# Analogs.net
KiCad netlist of a schematic drawn in Altium Designer
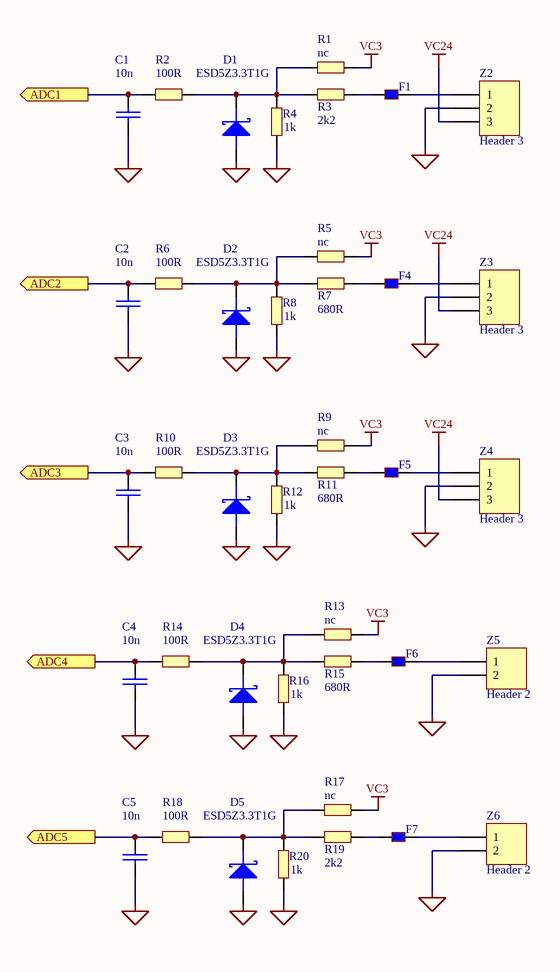
[diagram p0: Analogs.SchDoc]

(export (version "E")
  (design (tool "Eeschema 10.0.6"))
  (components
    (comp (ref "C1")
      (value "10n")
      (footprint "0805C")
      (description "Capacitor")
      (libsource (lib "*") (part "CAP"))
    )
    (comp (ref "C2")
      (value "10n")
      (footprint "0805C")
      (description "Capacitor")
      (libsource (lib "*") (part "CAP"))
    )
    (comp (ref "C3")
      (value "10n")
      (footprint "0805C")
      (description "Capacitor")
      (libsource (lib "*") (part "CAP"))
    )
    (comp (ref "C4")
      (value "10n")
      (footprint "0805C")
      (description "Capacitor")
      (libsource (lib "*") (part "CAP"))
    )
    (comp (ref "C5")
      (value "10n")
      (footprint "0805C")
      (description "Capacitor")
      (libsource (lib "*") (part "CAP"))
    )
    (comp (ref "D1")
      (value "ESD5Z3.3T1G")
      (footprint "SOD_523")
      (libsource (lib "*") (part "DIODE SCHOTTKY"))
    )
    (comp (ref "D2")
      (value "ESD5Z3.3T1G")
      (footprint "SOD_523")
      (libsource (lib "*") (part "DIODE SCHOTTKY"))
    )
    (comp (ref "D3")
      (value "ESD5Z3.3T1G")
      (footprint "SOD_523")
      (libsource (lib "*") (part "DIODE SCHOTTKY"))
    )
    (comp (ref "D4")
      (value "ESD5Z3.3T1G")
      (footprint "SOD_523")
      (libsource (lib "*") (part "DIODE SCHOTTKY"))
    )
    (comp (ref "D5")
      (value "ESD5Z3.3T1G")
      (footprint "SOD_523")
      (libsource (lib "*") (part "DIODE SCHOTTKY"))
    )
    (comp (ref "F1")
      (value "BLM18BB141SN1D")
      (footprint "0805L")
      (description "Koralik ferrytowy")
      (libsource (lib "*") (part "1812"))
    )
    (comp (ref "F4")
      (value "BLM18BB141SN1D")
      (footprint "0805L")
      (description "Koralik ferrytowy")
      (libsource (lib "*") (part "1812"))
    )
    (comp (ref "F5")
      (value "BLM18BB141SN1D")
      (footprint "0805L")
      (description "Koralik ferrytowy")
      (libsource (lib "*") (part "1812"))
    )
    (comp (ref "F6")
      (value "BLM18BB141SN1D")
      (footprint "0805L")
      (description "Koralik ferrytowy")
      (libsource (lib "*") (part "1812"))
    )
    (comp (ref "F7")
      (value "BLM18BB141SN1D")
      (footprint "0805L")
      (description "Koralik ferrytowy")
      (libsource (lib "*") (part "1812"))
    )
    (comp (ref "R1") (value "nc") (footprint "0805R") (libsource (lib "*") (part "RES3")))
    (comp (ref "R2") (value "100R") (footprint "0805R") (libsource (lib "") (part "RES3_2")))
    (comp (ref "R3") (value "2k2") (footprint "0805R") (libsource (lib "*") (part "RES3")))
    (comp (ref "R4") (value "1k") (footprint "0805R") (libsource (lib "") (part "RES3_1")))
    (comp (ref "R5") (value "nc") (footprint "0805R") (libsource (lib "*") (part "RES3")))
    (comp (ref "R6") (value "100R") (footprint "0805R") (libsource (lib "") (part "RES3_2")))
    (comp (ref "R7") (value "680R") (footprint "0805R") (libsource (lib "*") (part "RES3")))
    (comp (ref "R8") (value "1k") (footprint "0805R") (libsource (lib "") (part "RES3_1")))
    (comp (ref "R9") (value "nc") (footprint "0805R") (libsource (lib "*") (part "RES3")))
    (comp (ref "R10") (value "100R") (footprint "0805R") (libsource (lib "") (part "RES3_2")))
    (comp (ref "R11") (value "680R") (footprint "0805R") (libsource (lib "*") (part "RES3")))
    (comp (ref "R12") (value "1k") (footprint "0805R") (libsource (lib "") (part "RES3_1")))
    (comp (ref "R13") (value "nc") (footprint "0805R") (libsource (lib "*") (part "RES3")))
    (comp (ref "R14") (value "100R") (footprint "0805R") (libsource (lib "") (part "RES3_2")))
    (comp (ref "R15") (value "680R") (footprint "0805R") (libsource (lib "*") (part "RES3")))
    (comp (ref "R16") (value "1k") (footprint "0805R") (libsource (lib "") (part "RES3_1")))
    (comp (ref "R17") (value "nc") (footprint "0805R") (libsource (lib "*") (part "RES3")))
    (comp (ref "R18") (value "100R") (footprint "0805R") (libsource (lib "") (part "RES3_2")))
    (comp (ref "R19") (value "2k2") (footprint "0805R") (libsource (lib "*") (part "RES3")))
    (comp (ref "R20") (value "1k") (footprint "0805R") (libsource (lib "") (part "RES3_1")))
    (comp (ref "Z2")
      (value "Header 3")
      (footprint "ARC-L-3-3.5")
      (description "Header, 3-Pin")
      (fields (field (name "PUBLISHER") "Altium Limited"))
      (libsource (lib "Miscellaneous Connectors") (part "Header 3"))
    )
    (comp (ref "Z3")
      (value "Header 3")
      (footprint "ARC-L-3-3.5")
      (description "Header, 3-Pin")
      (fields (field (name "PUBLISHER") "Altium Limited"))
      (libsource (lib "Miscellaneous Connectors") (part "Header 3"))
    )
    (comp (ref "Z4")
      (value "Header 3")
      (footprint "ARC-L-3-3.5")
      (description "Header, 3-Pin")
      (fields (field (name "PUBLISHER") "Altium Limited"))
      (libsource (lib "Miscellaneous Connectors") (part "Header 3"))
    )
    (comp (ref "Z5")
      (value "Header 2")
      (footprint "ARC-L-2-3.5")
      (description "Header, 2-Pin")
      (fields (field (name "PUBLISHER") "Altium Limited"))
      (libsource (lib "Miscellaneous Connectors") (part "Header 2"))
    )
    (comp (ref "Z6")
      (value "Header 2")
      (footprint "ARC-L-2-3.5")
      (description "Header, 2-Pin")
      (fields (field (name "PUBLISHER") "Altium Limited"))
      (libsource (lib "Miscellaneous Connectors") (part "Header 2"))
    )
  )
  (nets
    (net (code "1") (name "/ADC1") (class "Default")
      (node (ref "C1") (pin "1") (pinfunction "1_1") (pintype "passive"))
      (node (ref "R2") (pin "1") (pintype "passive"))
    )
    (net (code "2") (name "/ADC2") (class "Default")
      (node (ref "C2") (pin "1") (pinfunction "1_1") (pintype "passive"))
      (node (ref "R6") (pin "1") (pintype "passive"))
    )
    (net (code "3") (name "/ADC3") (class "Default")
      (node (ref "C3") (pin "1") (pinfunction "1_1") (pintype "passive"))
      (node (ref "R10") (pin "1") (pintype "passive"))
    )
    (net (code "4") (name "/ADC4") (class "Default")
      (node (ref "C4") (pin "1") (pinfunction "1_1") (pintype "passive"))
      (node (ref "R14") (pin "1") (pintype "passive"))
    )
    (net (code "5") (name "/ADC5") (class "Default")
      (node (ref "C5") (pin "1") (pinfunction "1_1") (pintype "passive"))
      (node (ref "R18") (pin "1") (pintype "passive"))
    )
    (net (code "6") (name "AGND") (class "Default")
      (node (ref "C1") (pin "2") (pinfunction "2_2") (pintype "passive"))
      (node (ref "C2") (pin "2") (pinfunction "2_2") (pintype "passive"))
      (node (ref "C3") (pin "2") (pinfunction "2_2") (pintype "passive"))
      (node (ref "C4") (pin "2") (pinfunction "2_2") (pintype "passive"))
      (node (ref "C5") (pin "2") (pinfunction "2_2") (pintype "passive"))
      (node (ref "D1") (pin "A") (pinfunction "A_A") (pintype "passive"))
      (node (ref "D2") (pin "A") (pinfunction "A_A") (pintype "passive"))
      (node (ref "D3") (pin "A") (pinfunction "A_A") (pintype "passive"))
      (node (ref "D4") (pin "A") (pinfunction "A_A") (pintype "passive"))
      (node (ref "D5") (pin "A") (pinfunction "A_A") (pintype "passive"))
      (node (ref "R12") (pin "1") (pintype "passive"))
      (node (ref "R16") (pin "1") (pintype "passive"))
      (node (ref "R20") (pin "1") (pintype "passive"))
      (node (ref "R4") (pin "1") (pintype "passive"))
      (node (ref "R8") (pin "1") (pintype "passive"))
      (node (ref "Z2") (pin "2") (pinfunction "2_2") (pintype "passive"))
      (node (ref "Z3") (pin "2") (pinfunction "2_2") (pintype "passive"))
      (node (ref "Z4") (pin "2") (pinfunction "2_2") (pintype "passive"))
      (node (ref "Z5") (pin "2") (pinfunction "2_2") (pintype "passive"))
      (node (ref "Z6") (pin "2") (pinfunction "2_2") (pintype "passive"))
    )
    (net (code "7") (name "Net-(D1-PadK)") (class "Default")
      (node (ref "D1") (pin "K") (pinfunction "K_K") (pintype "passive"))
      (node (ref "R1") (pin "2") (pintype "passive"))
      (node (ref "R2") (pin "2") (pintype "passive"))
      (node (ref "R3") (pin "2") (pintype "passive"))
      (node (ref "R4") (pin "2") (pintype "passive"))
    )
    (net (code "8") (name "Net-(D2-PadK)") (class "Default")
      (node (ref "D2") (pin "K") (pinfunction "K_K") (pintype "passive"))
      (node (ref "R5") (pin "2") (pintype "passive"))
      (node (ref "R6") (pin "2") (pintype "passive"))
      (node (ref "R7") (pin "2") (pintype "passive"))
      (node (ref "R8") (pin "2") (pintype "passive"))
    )
    (net (code "9") (name "Net-(D3-PadK)") (class "Default")
      (node (ref "D3") (pin "K") (pinfunction "K_K") (pintype "passive"))
      (node (ref "R10") (pin "2") (pintype "passive"))
      (node (ref "R11") (pin "2") (pintype "passive"))
      (node (ref "R12") (pin "2") (pintype "passive"))
      (node (ref "R9") (pin "2") (pintype "passive"))
    )
    (net (code "10") (name "Net-(D4-PadK)") (class "Default")
      (node (ref "D4") (pin "K") (pinfunction "K_K") (pintype "passive"))
      (node (ref "R13") (pin "2") (pintype "passive"))
      (node (ref "R14") (pin "2") (pintype "passive"))
      (node (ref "R15") (pin "2") (pintype "passive"))
      (node (ref "R16") (pin "2") (pintype "passive"))
    )
    (net (code "11") (name "Net-(D5-PadK)") (class "Default")
      (node (ref "D5") (pin "K") (pinfunction "K_K") (pintype "passive"))
      (node (ref "R17") (pin "2") (pintype "passive"))
      (node (ref "R18") (pin "2") (pintype "passive"))
      (node (ref "R19") (pin "2") (pintype "passive"))
      (node (ref "R20") (pin "2") (pintype "passive"))
    )
    (net (code "12") (name "Net-(F1-Pad1)") (class "Default")
      (node (ref "F1") (pin "1") (pintype "passive"))
      (node (ref "Z2") (pin "1") (pinfunction "1_1") (pintype "passive"))
    )
    (net (code "13") (name "Net-(F1-Pad2)") (class "Default")
      (node (ref "F1") (pin "2") (pintype "passive"))
      (node (ref "R3") (pin "1") (pintype "passive"))
    )
    (net (code "14") (name "Net-(F4-Pad1)") (class "Default")
      (node (ref "F4") (pin "1") (pintype "passive"))
      (node (ref "Z3") (pin "1") (pinfunction "1_1") (pintype "passive"))
    )
    (net (code "15") (name "Net-(F4-Pad2)") (class "Default")
      (node (ref "F4") (pin "2") (pintype "passive"))
      (node (ref "R7") (pin "1") (pintype "passive"))
    )
    (net (code "16") (name "Net-(F5-Pad1)") (class "Default")
      (node (ref "F5") (pin "1") (pintype "passive"))
      (node (ref "Z4") (pin "1") (pinfunction "1_1") (pintype "passive"))
    )
    (net (code "17") (name "Net-(F5-Pad2)") (class "Default")
      (node (ref "F5") (pin "2") (pintype "passive"))
      (node (ref "R11") (pin "1") (pintype "passive"))
    )
    (net (code "18") (name "Net-(F6-Pad1)") (class "Default")
      (node (ref "F6") (pin "1") (pintype "passive"))
      (node (ref "Z5") (pin "1") (pinfunction "1_1") (pintype "passive"))
    )
    (net (code "19") (name "Net-(F6-Pad2)") (class "Default")
      (node (ref "F6") (pin "2") (pintype "passive"))
      (node (ref "R15") (pin "1") (pintype "passive"))
    )
    (net (code "20") (name "Net-(F7-Pad1)") (class "Default")
      (node (ref "F7") (pin "1") (pintype "passive"))
      (node (ref "Z6") (pin "1") (pinfunction "1_1") (pintype "passive"))
    )
    (net (code "21") (name "Net-(F7-Pad2)") (class "Default")
      (node (ref "F7") (pin "2") (pintype "passive"))
      (node (ref "R19") (pin "1") (pintype "passive"))
    )
    (net (code "22") (name "VC3") (class "Default")
      (node (ref "R1") (pin "1") (pintype "passive"))
      (node (ref "R13") (pin "1") (pintype "passive"))
      (node (ref "R17") (pin "1") (pintype "passive"))
      (node (ref "R5") (pin "1") (pintype "passive"))
      (node (ref "R9") (pin "1") (pintype "passive"))
    )
    (net (code "23") (name "VC24") (class "Default")
      (node (ref "Z2") (pin "3") (pinfunction "3_3") (pintype "passive"))
      (node (ref "Z3") (pin "3") (pinfunction "3_3") (pintype "passive"))
      (node (ref "Z4") (pin "3") (pinfunction "3_3") (pintype "passive"))
    )
  )
)
